# SCH_projectpt2_2025-10-31.net
KiCad netlist of a schematic drawn in EasyEDA
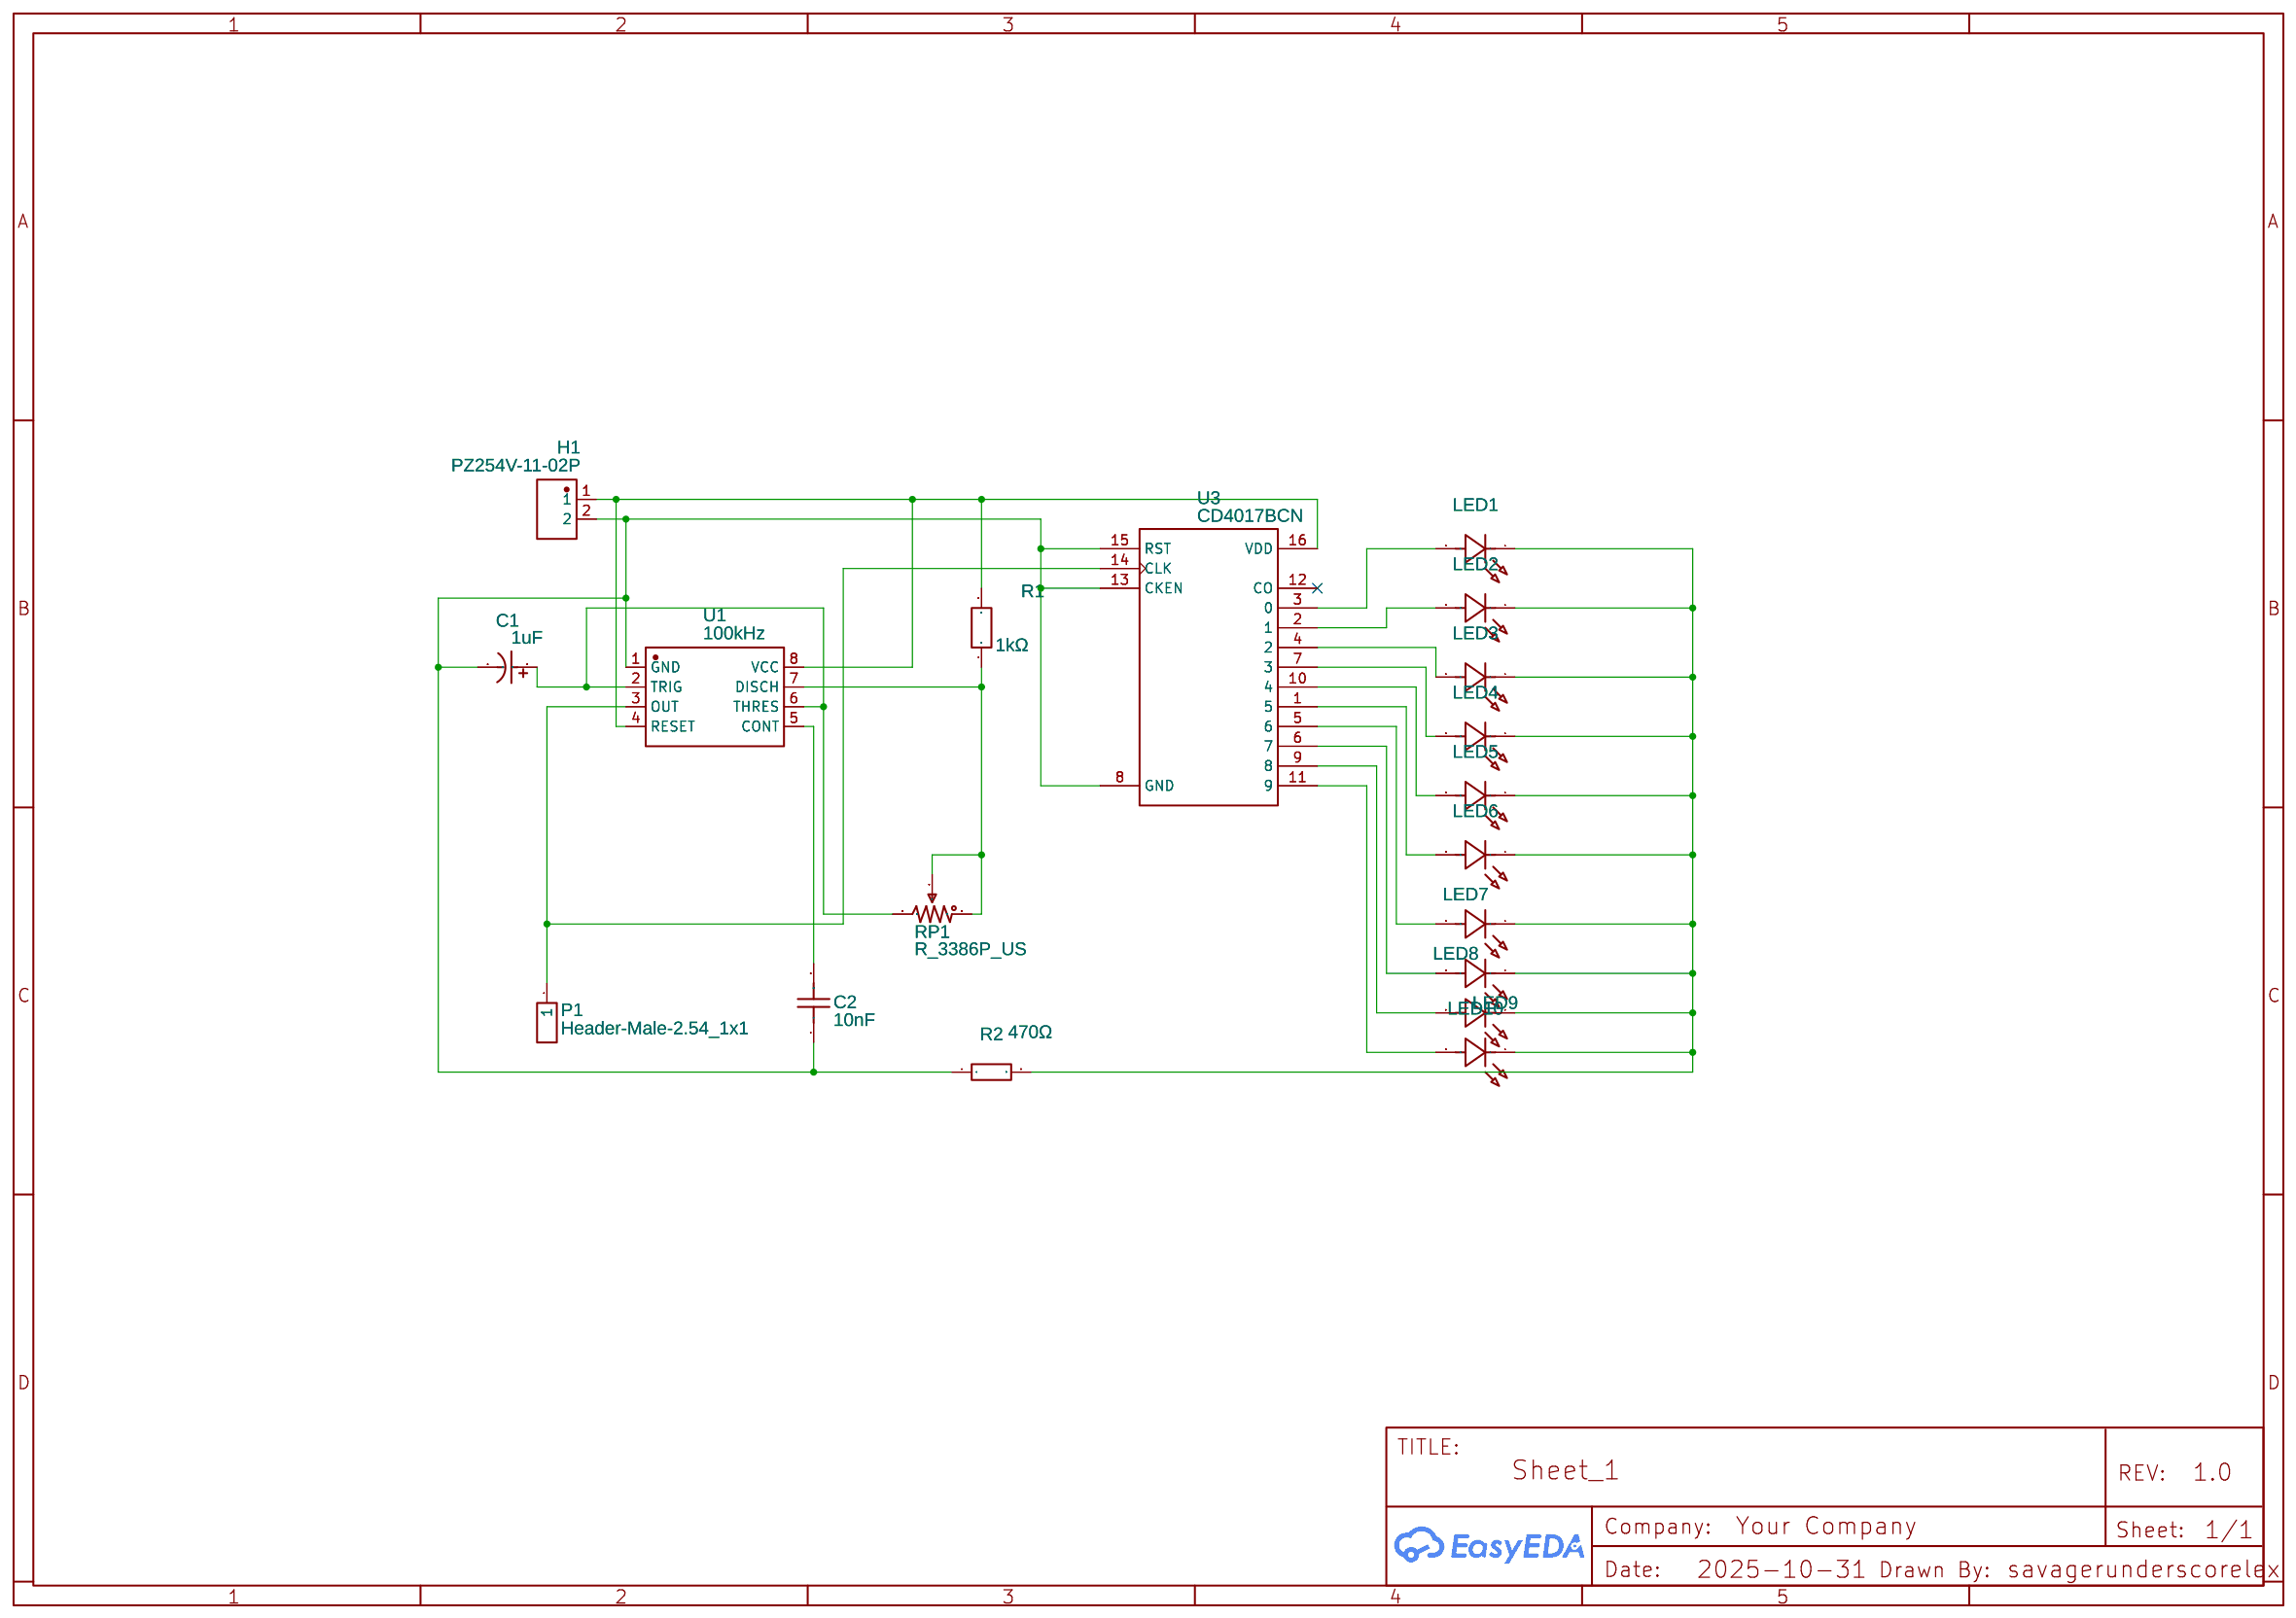
[diagram p0: schematic sheet]

(export (version "E")
  (design (tool "Eeschema 10.0.6"))
  (components
    (comp (ref "C1")
      (value "1uF")
      (fields (field (name "Manufacturer Part") "KF010M050C110A") (field (name "Manufacturer") "CapXon(丰宾)"))
      (libsource (lib "") (part "KF010M050C110A"))
    )
    (comp (ref "C2")
      (value "10nF")
      (fields (field (name "Manufacturer Part") "N09F1B103MN0B0S0N0") (field (name "Manufacturer") "STE(松田)"))
      (libsource (lib "") (part "N09F1B103MN0B0S0N0"))
    )
    (comp (ref "H1")
      (value "PZ254V-11-02P")
      (fields (field (name "Manufacturer") "XFCN(兴飞)"))
      (libsource (lib "") (part "PZ254V-11-02P"))
    )
    (comp (ref "LED1")
      (value "TZ-L2-05YYBO3TDJ15-001")
      (fields (field (name "Manufacturer") "TUOZHAN(拓展光电)"))
      (libsource (lib "") (part "TZ-L2-05YYBO3TDJ15-001"))
    )
    (comp (ref "LED2")
      (value "TZ-L2-05YYBO3TDJ15-001")
      (fields (field (name "Manufacturer") "TUOZHAN(拓展光电)"))
      (libsource (lib "") (part "TZ-L2-05YYBO3TDJ15-001"))
    )
    (comp (ref "LED3")
      (value "TZ-L2-05YYBO3TDJ15-001")
      (fields (field (name "Manufacturer") "TUOZHAN(拓展光电)"))
      (libsource (lib "") (part "TZ-L2-05YYBO3TDJ15-001"))
    )
    (comp (ref "LED4")
      (value "TZ-L2-05YYBO3TDJ15-001")
      (fields (field (name "Manufacturer") "TUOZHAN(拓展光电)"))
      (libsource (lib "") (part "TZ-L2-05YYBO3TDJ15-001"))
    )
    (comp (ref "LED5")
      (value "TZ-L2-05YYBO3TDJ15-001")
      (fields (field (name "Manufacturer") "TUOZHAN(拓展光电)"))
      (libsource (lib "") (part "TZ-L2-05YYBO3TDJ15-001"))
    )
    (comp (ref "LED6")
      (value "TZ-L2-05YYBO3TDJ15-001")
      (fields (field (name "Manufacturer") "TUOZHAN(拓展光电)"))
      (libsource (lib "") (part "TZ-L2-05YYBO3TDJ15-001"))
    )
    (comp (ref "LED7")
      (value "TZ-L2-05YYBO3TDJ15-001")
      (fields (field (name "Manufacturer") "TUOZHAN(拓展光电)"))
      (libsource (lib "") (part "TZ-L2-05YYBO3TDJ15-001"))
    )
    (comp (ref "LED8")
      (value "TZ-L2-05YYBO3TDJ15-001")
      (fields (field (name "Manufacturer") "TUOZHAN(拓展光电)"))
      (libsource (lib "") (part "TZ-L2-05YYBO3TDJ15-001"))
    )
    (comp (ref "LED9")
      (value "TZ-L2-05YYBO3TDJ15-001")
      (fields (field (name "Manufacturer") "TUOZHAN(拓展光电)"))
      (libsource (lib "") (part "TZ-L2-05YYBO3TDJ15-001"))
    )
    (comp (ref "LED10")
      (value "TZ-L2-05YYBO3TDJ15-001")
      (fields (field (name "Manufacturer") "TUOZHAN(拓展光电)"))
      (libsource (lib "") (part "TZ-L2-05YYBO3TDJ15-001"))
    )
    (comp (ref "P1")
      (value "Header-Male-2.54_1x1")
      (fields (field (name "Manufacturer Part") "2.54-1*1P针") (field (name "Manufacturer") "BOOMELE(博穆精密)"))
      (libsource (lib "") (part "Header-Male-2.54_1x1"))
    )
    (comp (ref "R1")
      (value "1kΩ")
      (fields (field (name "Manufacturer Part") "MF1/4W-1KΩ±1%T52") (field (name "Manufacturer") "华星机电"))
      (libsource (lib "") (part "MF1/4W-1KΩ±1%T52"))
    )
    (comp (ref "R2")
      (value "470Ω")
      (fields
        (field (name "Manufacturer Part") "MFR0W4F4700A50")
        (field (name "Manufacturer") "UNI-ROYAL(厚声)")
      )
      (libsource (lib "") (part "MFR0W4F4700A50"))
    )
    (comp (ref "RP1") (value "R_3386P_US") (libsource (lib "") (part "R_3386P_US")))
    (comp (ref "U1")
      (value "100kHz")
      (fields (field (name "Manufacturer Part") "NE555P") (field (name "Manufacturer") "TI(德州仪器)"))
      (libsource (lib "") (part "NE555P"))
    )
    (comp (ref "U3") (value "CD4017BCN") (libsource (lib "") (part "CD4017BCN")))
  )
  (nets
    (net (code "1") (name "Net-(LED1-+)") (class "Default")
      (node (ref "LED1") (pin "2") (pinfunction "+_2") (pintype "unspecified"))
      (node (ref "U3") (pin "3") (pinfunction "0_3") (pintype "output"))
    )
    (net (code "2") (name "Net-(LED1--)") (class "Default")
      (node (ref "LED1") (pin "1") (pinfunction "-_1") (pintype "unspecified"))
      (node (ref "LED10") (pin "1") (pinfunction "-_1") (pintype "unspecified"))
      (node (ref "LED2") (pin "1") (pinfunction "-_1") (pintype "unspecified"))
      (node (ref "LED3") (pin "1") (pinfunction "-_1") (pintype "unspecified"))
      (node (ref "LED4") (pin "1") (pinfunction "-_1") (pintype "unspecified"))
      (node (ref "LED5") (pin "1") (pinfunction "-_1") (pintype "unspecified"))
      (node (ref "LED6") (pin "1") (pinfunction "-_1") (pintype "unspecified"))
      (node (ref "LED7") (pin "1") (pinfunction "-_1") (pintype "unspecified"))
      (node (ref "LED8") (pin "1") (pinfunction "-_1") (pintype "unspecified"))
      (node (ref "LED9") (pin "1") (pinfunction "-_1") (pintype "unspecified"))
      (node (ref "R2") (pin "2") (pinfunction "2_2") (pintype "input"))
    )
    (net (code "3") (name "Net-(LED2-+)") (class "Default")
      (node (ref "LED2") (pin "2") (pinfunction "+_2") (pintype "unspecified"))
      (node (ref "U3") (pin "2") (pinfunction "1_2") (pintype "output"))
    )
    (net (code "4") (name "Net-(LED3-+)") (class "Default")
      (node (ref "LED3") (pin "2") (pinfunction "+_2") (pintype "unspecified"))
      (node (ref "U3") (pin "4") (pinfunction "2_4") (pintype "output"))
    )
    (net (code "5") (name "Net-(LED4-+)") (class "Default")
      (node (ref "LED4") (pin "2") (pinfunction "+_2") (pintype "unspecified"))
      (node (ref "U3") (pin "7") (pinfunction "3_7") (pintype "output"))
    )
    (net (code "6") (name "Net-(LED5-+)") (class "Default")
      (node (ref "LED5") (pin "2") (pinfunction "+_2") (pintype "unspecified"))
      (node (ref "U3") (pin "10") (pinfunction "4_10") (pintype "output"))
    )
    (net (code "7") (name "Net-(LED6-+)") (class "Default")
      (node (ref "LED6") (pin "2") (pinfunction "+_2") (pintype "unspecified"))
      (node (ref "U3") (pin "1") (pinfunction "5_1") (pintype "output"))
    )
    (net (code "8") (name "Net-(LED7-+)") (class "Default")
      (node (ref "LED7") (pin "2") (pinfunction "+_2") (pintype "unspecified"))
      (node (ref "U3") (pin "5") (pinfunction "6_5") (pintype "output"))
    )
    (net (code "9") (name "Net-(LED8-+)") (class "Default")
      (node (ref "LED8") (pin "2") (pinfunction "+_2") (pintype "unspecified"))
      (node (ref "U3") (pin "6") (pinfunction "7_6") (pintype "output"))
    )
    (net (code "10") (name "Net-(LED9-+)") (class "Default")
      (node (ref "LED9") (pin "2") (pinfunction "+_2") (pintype "unspecified"))
      (node (ref "U3") (pin "9") (pinfunction "8_9") (pintype "output"))
    )
    (net (code "11") (name "Net-(LED10-+)") (class "Default")
      (node (ref "LED10") (pin "2") (pinfunction "+_2") (pintype "unspecified"))
      (node (ref "U3") (pin "11") (pinfunction "9_11") (pintype "output"))
    )
    (net (code "12") (name "Net-(U1-CONT)") (class "Default")
      (node (ref "C2") (pin "2") (pinfunction "2_2") (pintype "unspecified"))
      (node (ref "U1") (pin "5") (pinfunction "CONT_5") (pintype "unspecified"))
    )
    (net (code "13") (name "Net-(U1-DISCH)") (class "Default")
      (node (ref "R1") (pin "1") (pinfunction "1_1") (pintype "unspecified"))
      (node (ref "RP1") (pin "1") (pinfunction "1_1") (pintype "unspecified"))
      (node (ref "RP1") (pin "2") (pinfunction "2_2") (pintype "unspecified"))
      (node (ref "U1") (pin "7") (pinfunction "DISCH_7") (pintype "unspecified"))
    )
    (net (code "14") (name "Net-(U1-GND)") (class "Default")
      (node (ref "C1") (pin "2") (pinfunction "2_2") (pintype "input"))
      (node (ref "C2") (pin "1") (pinfunction "1_1") (pintype "unspecified"))
      (node (ref "H1") (pin "2") (pinfunction "2_2") (pintype "unspecified"))
      (node (ref "R2") (pin "1") (pinfunction "1_1") (pintype "input"))
      (node (ref "U1") (pin "1") (pinfunction "GND_1") (pintype "unspecified"))
      (node (ref "U3") (pin "13") (pinfunction "CKEN_13") (pintype "unspecified"))
      (node (ref "U3") (pin "15") (pinfunction "RST_15") (pintype "unspecified"))
      (node (ref "U3") (pin "8") (pinfunction "GND_8") (pintype "passive"))
    )
    (net (code "15") (name "Net-(U1-OUT)") (class "Default")
      (node (ref "P1") (pin "1") (pinfunction "1_1") (pintype "input"))
      (node (ref "U1") (pin "3") (pinfunction "OUT_3") (pintype "unspecified"))
      (node (ref "U3") (pin "14") (pinfunction "CLK_14") (pintype "unspecified"))
    )
    (net (code "16") (name "Net-(U1-RESET)") (class "Default")
      (node (ref "H1") (pin "1") (pinfunction "1_1") (pintype "unspecified"))
      (node (ref "R1") (pin "2") (pinfunction "2_2") (pintype "unspecified"))
      (node (ref "U1") (pin "4") (pinfunction "RESET_4") (pintype "unspecified"))
      (node (ref "U1") (pin "8") (pinfunction "VCC_8") (pintype "unspecified"))
      (node (ref "U3") (pin "16") (pinfunction "VDD_16") (pintype "passive"))
    )
    (net (code "17") (name "Net-(U1-THRES)") (class "Default")
      (node (ref "C1") (pin "1") (pinfunction "1_1") (pintype "input"))
      (node (ref "RP1") (pin "3") (pinfunction "3_3") (pintype "unspecified"))
      (node (ref "U1") (pin "2") (pinfunction "TRIG_2") (pintype "unspecified"))
      (node (ref "U1") (pin "6") (pinfunction "THRES_6") (pintype "unspecified"))
    )
    (net (code "18") (name "unconnected-(U3-CO-Pad12)") (class "Default")
      (node (ref "U3") (pin "12") (pinfunction "CO_12") (pintype "output+no_connect"))
    )
  )
)
